# PCB_Power.net
KiCad netlist of a schematic drawn in EAGLE
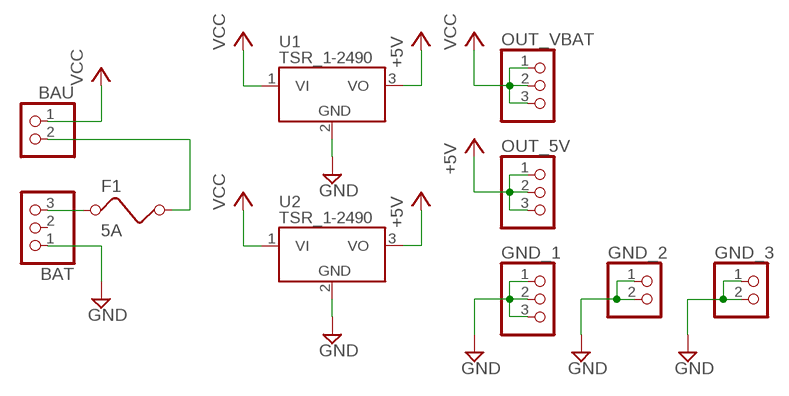
[diagram p0: schematic, sheet 1]

(export (version "E")
  (design (tool "Eeschema 10.0.6"))
  (components
    (comp (ref "BAT")
      (value "TERMINALBLOCK_1X3-5.0MM")
      (footprint "eagle-import:TERMINALBLOCK_1X3-5.0MM")
      (libsource (lib "eagle-import") (part "TERMINALBLOCK_1X3-5.0MM"))
    )
    (comp (ref "BAU")
      (value "TERMINALBLOCK_1X2-5.0MM")
      (footprint "eagle-import:TERMINALBLOCK_1X2-5.0MM")
      (libsource (lib "eagle-import") (part "TERMINALBLOCK_1X2-5.0MM"))
    )
    (comp (ref "F1")
      (value "5A")
      (footprint "eagle-import:FUSE")
      (libsource (lib "eagle-import") (part "FUSE"))
    )
    (comp (ref "GND_1")
      (value "TERMINALBLOCK_1X3-5.0MM")
      (footprint "eagle-import:TERMINALBLOCK_1X3-5.0MM")
      (libsource (lib "eagle-import") (part "TERMINALBLOCK_1X3-5.0MM"))
    )
    (comp (ref "GND_2")
      (value "TERMINALBLOCK_1X2-5.0MM")
      (footprint "eagle-import:TERMINALBLOCK_1X2-5.0MM")
      (libsource (lib "eagle-import") (part "TERMINALBLOCK_1X2-5.0MM"))
    )
    (comp (ref "GND_3")
      (value "TERMINALBLOCK_1X2-5.0MM")
      (footprint "eagle-import:TERMINALBLOCK_1X2-5.0MM")
      (libsource (lib "eagle-import") (part "TERMINALBLOCK_1X2-5.0MM"))
    )
    (comp (ref "OUT_5V")
      (value "TERMINALBLOCK_1X3-5.0MM")
      (footprint "eagle-import:TERMINALBLOCK_1X3-5.0MM")
      (libsource (lib "eagle-import") (part "TERMINALBLOCK_1X3-5.0MM"))
    )
    (comp (ref "OUT_VBAT")
      (value "TERMINALBLOCK_1X3-5.0MM")
      (footprint "eagle-import:TERMINALBLOCK_1X3-5.0MM")
      (libsource (lib "eagle-import") (part "TERMINALBLOCK_1X3-5.0MM"))
    )
    (comp (ref "U1")
      (value "TSR_1-2490")
      (footprint "eagle-import:TSR-1")
      (libsource (lib "eagle-import") (part "TSR_1-2490"))
    )
    (comp (ref "U2")
      (value "TSR_1-2490")
      (footprint "eagle-import:TSR-1")
      (libsource (lib "eagle-import") (part "TSR_1-2490"))
    )
  )
  (nets
    (net (code "1") (name "+5V") (class "Default")
      (node (ref "OUT_5V") (pin "1") (pinfunction "1_1") (pintype "passive"))
      (node (ref "OUT_5V") (pin "2") (pinfunction "2_2") (pintype "passive"))
      (node (ref "OUT_5V") (pin "3") (pinfunction "3_3") (pintype "passive"))
      (node (ref "U1") (pin "3") (pinfunction "VO_3") (pintype "power_in"))
      (node (ref "U2") (pin "3") (pinfunction "VO_3") (pintype "power_in"))
    )
    (net (code "2") (name "GND") (class "Default")
      (node (ref "BAT") (pin "1") (pinfunction "1_1") (pintype "passive"))
      (node (ref "GND_1") (pin "1") (pinfunction "1_1") (pintype "passive"))
      (node (ref "GND_1") (pin "2") (pinfunction "2_2") (pintype "passive"))
      (node (ref "GND_1") (pin "3") (pinfunction "3_3") (pintype "passive"))
      (node (ref "GND_2") (pin "1") (pinfunction "1_1") (pintype "passive"))
      (node (ref "GND_2") (pin "2") (pinfunction "2_2") (pintype "passive"))
      (node (ref "GND_3") (pin "1") (pinfunction "1_1") (pintype "passive"))
      (node (ref "GND_3") (pin "2") (pinfunction "2_2") (pintype "passive"))
      (node (ref "U1") (pin "2") (pinfunction "GND_2") (pintype "power_in"))
      (node (ref "U2") (pin "2") (pinfunction "GND_2") (pintype "power_in"))
    )
    (net (code "3") (name "Net-(BAT-Pad3)") (class "Default")
      (node (ref "BAT") (pin "3") (pinfunction "3_3") (pintype "passive"))
      (node (ref "F1") (pin "1") (pinfunction "1_1") (pintype "passive"))
    )
    (net (code "4") (name "Net-(BAU-Pad2)") (class "Default")
      (node (ref "BAU") (pin "2") (pinfunction "2_2") (pintype "passive"))
      (node (ref "F1") (pin "2") (pinfunction "2_2") (pintype "passive"))
    )
    (net (code "5") (name "VCC") (class "Default")
      (node (ref "BAU") (pin "1") (pinfunction "1_1") (pintype "passive"))
      (node (ref "OUT_VBAT") (pin "1") (pinfunction "1_1") (pintype "passive"))
      (node (ref "OUT_VBAT") (pin "2") (pinfunction "2_2") (pintype "passive"))
      (node (ref "OUT_VBAT") (pin "3") (pinfunction "3_3") (pintype "passive"))
      (node (ref "U1") (pin "1") (pinfunction "VI_1") (pintype "power_in"))
      (node (ref "U2") (pin "1") (pinfunction "VI_1") (pintype "power_in"))
    )
    (net (code "6") (name "unconnected-(BAT-Pad2)") (class "Default")
      (node (ref "BAT") (pin "2") (pinfunction "2_2") (pintype "passive"))
    )
  )
)
